# lime2_adapter.net
KiCad netlist of a schematic drawn in EAGLE
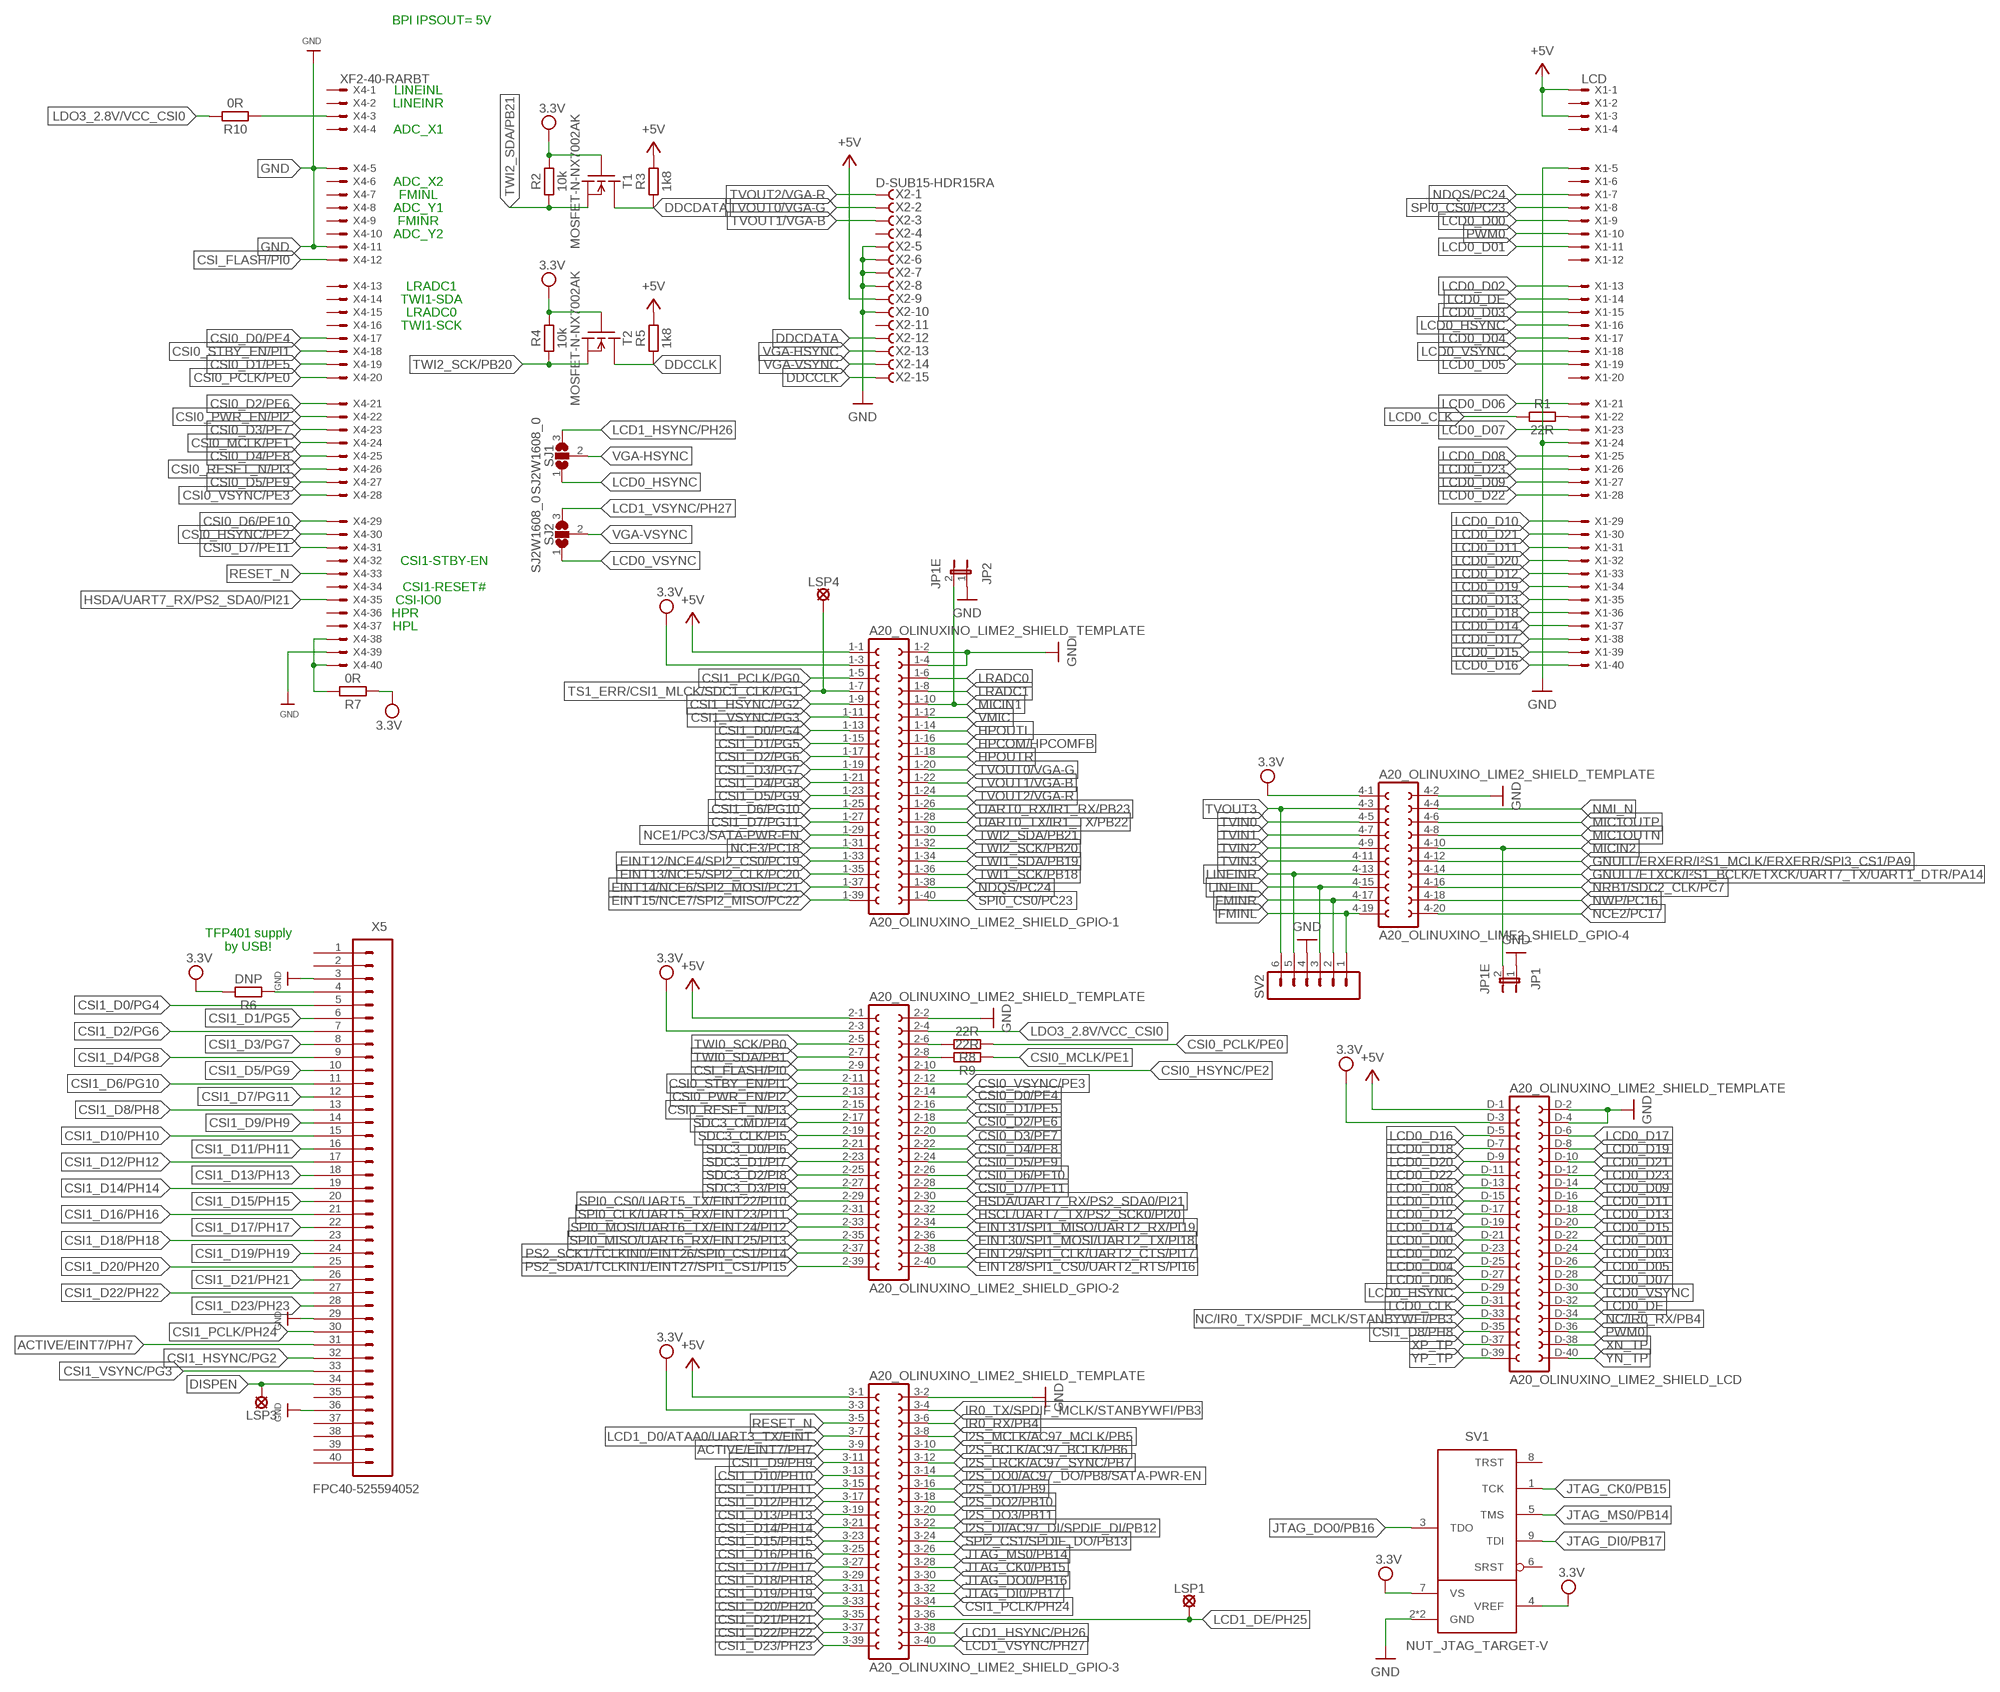
[diagram p0: schematic, sheet 1]

(export (version "E")
  (design (tool "Eeschema 10.0.6"))
  (components
    (comp (ref "A20_OLINUXINO_LIME2_SHIELD")
      (value "A20_OLINUXINO_LIME2_SHIELD_TEMPLATE")
      (footprint "eagle-import:A20_OLINUXINO_LIME2_SHIELD")
      (libsource (lib "eagle-import") (part "A20_OLINUXINO_LIME2_SHIELD_TEMPLATE"))
    )
    (comp (ref "JP1")
      (value "JP1E")
      (footprint "eagle-import:JP1")
      (libsource (lib "eagle-import") (part "JP1E"))
    )
    (comp (ref "JP2")
      (value "JP1E")
      (footprint "eagle-import:JP1")
      (libsource (lib "eagle-import") (part "JP1E"))
    )
    (comp (ref "LSP1")
      (value "LSP-PAD15")
      (footprint "eagle-import:PAD15")
      (libsource (lib "eagle-import") (part "LSP-PAD15"))
    )
    (comp (ref "LSP3")
      (value "LSP-PAD15")
      (footprint "eagle-import:PAD15")
      (libsource (lib "eagle-import") (part "LSP-PAD15"))
    )
    (comp (ref "LSP4")
      (value "LSP-PAD15")
      (footprint "eagle-import:PAD15")
      (libsource (lib "eagle-import") (part "LSP-PAD15"))
    )
    (comp (ref "R1")
      (value "22R")
      (footprint "eagle-import:RES1608X55N")
      (libsource (lib "eagle-import") (part "R-EU_RES1608X55N"))
    )
    (comp (ref "R2")
      (value "10k")
      (footprint "eagle-import:RES1608X55N")
      (libsource (lib "eagle-import") (part "R-EU_RES1608X55N"))
    )
    (comp (ref "R3")
      (value "1k8")
      (footprint "eagle-import:RES1608X55N")
      (libsource (lib "eagle-import") (part "R-EU_RES1608X55N"))
    )
    (comp (ref "R4")
      (value "10k")
      (footprint "eagle-import:RES1608X55N")
      (libsource (lib "eagle-import") (part "R-EU_RES1608X55N"))
    )
    (comp (ref "R5")
      (value "1k8")
      (footprint "eagle-import:RES1608X55N")
      (libsource (lib "eagle-import") (part "R-EU_RES1608X55N"))
    )
    (comp (ref "R6")
      (value "DNP")
      (footprint "eagle-import:RES1608X55N")
      (libsource (lib "eagle-import") (part "R-EU_RES1608X55N"))
    )
    (comp (ref "R7")
      (value "0R")
      (footprint "eagle-import:RES1608X55N")
      (libsource (lib "eagle-import") (part "R-EU_RES1608X55N"))
    )
    (comp (ref "R8")
      (value "22R")
      (footprint "eagle-import:RES1608X55N")
      (libsource (lib "eagle-import") (part "R-EU_RES1608X55N"))
    )
    (comp (ref "R9")
      (value "22R")
      (footprint "eagle-import:RES1608X55N")
      (libsource (lib "eagle-import") (part "R-EU_RES1608X55N"))
    )
    (comp (ref "R10")
      (value "0R")
      (footprint "eagle-import:RES1608X55N")
      (libsource (lib "eagle-import") (part "R-EU_RES1608X55N"))
    )
    (comp (ref "SJ1")
      (value "SJ2W1608_0")
      (footprint "eagle-import:SJ2_1608_0")
      (libsource (lib "eagle-import") (part "SJ2W1608_0"))
    )
    (comp (ref "SJ2")
      (value "SJ2W1608_0")
      (footprint "eagle-import:SJ2_1608_0")
      (libsource (lib "eagle-import") (part "SJ2W1608_0"))
    )
    (comp (ref "SV1")
      (value "NUT_JTAG_TARGET-V")
      (footprint "eagle-import:ML10")
      (libsource (lib "eagle-import") (part "NUT_JTAG_TARGET-V"))
    )
    (comp (ref "SV2")
      (value "MA06-1")
      (footprint "eagle-import:MA06-1")
      (libsource (lib "eagle-import") (part "MA06-1"))
    )
    (comp (ref "T1")
      (value "MOSFET-N-NX7002AK")
      (footprint "eagle-import:SOT95P230X110-3N")
      (libsource (lib "eagle-import") (part "MOSFET-N-?KNX7002A"))
    )
    (comp (ref "T2")
      (value "MOSFET-N-NX7002AK")
      (footprint "eagle-import:SOT95P230X110-3N")
      (libsource (lib "eagle-import") (part "MOSFET-N-?KNX7002A"))
    )
    (comp (ref "X1")
      (value "LCD")
      (footprint "eagle-import:4-1734839-0")
      (libsource (lib "eagle-import") (part "XF2-40?-RARBT"))
    )
    (comp (ref "X2")
      (value "D-SUB15-HDR15RA")
      (footprint "eagle-import:HDR15RA")
      (libsource (lib "eagle-import") (part "D-SUB15-HDR15RA"))
    )
    (comp (ref "X4")
      (value "XF2-40-RARBT")
      (footprint "eagle-import:4-1734839-0")
      (libsource (lib "eagle-import") (part "XF2-40?-RARBT"))
    )
    (comp (ref "X5")
      (value "FPC40-525594052")
      (footprint "eagle-import:525594052")
      (libsource (lib "eagle-import") (part "FPC40-525594052"))
    )
  )
  (nets
    (net (code "1") (name "+5V") (class "Default")
      (node (ref "A20_OLINUXINO_LIME2_SHIELD") (pin "1-1") (pinfunction "1_1-1") (pintype "passive"))
      (node (ref "A20_OLINUXINO_LIME2_SHIELD") (pin "2-1") (pinfunction "1_2-1") (pintype "passive"))
      (node (ref "A20_OLINUXINO_LIME2_SHIELD") (pin "3-1") (pinfunction "1_3-1") (pintype "passive"))
      (node (ref "A20_OLINUXINO_LIME2_SHIELD") (pin "D-1") (pinfunction "1_D-1") (pintype "passive"))
      (node (ref "R3") (pin "2") (pinfunction "2_2") (pintype "passive"))
      (node (ref "R5") (pin "2") (pinfunction "2_2") (pintype "passive"))
      (node (ref "X1") (pin "1") (pinfunction "MSV_1") (pintype "passive"))
      (node (ref "X1") (pin "3") (pinfunction "MS_3") (pintype "passive"))
      (node (ref "X2") (pin "9") (pinfunction "F_9") (pintype "passive"))
    )
    (net (code "2") (name "3.3V") (class "Default")
      (node (ref "A20_OLINUXINO_LIME2_SHIELD") (pin "1-3") (pinfunction "3_1-3") (pintype "passive"))
      (node (ref "A20_OLINUXINO_LIME2_SHIELD") (pin "2-3") (pinfunction "3_2-3") (pintype "passive"))
      (node (ref "A20_OLINUXINO_LIME2_SHIELD") (pin "3-3") (pinfunction "3_3-3") (pintype "passive"))
      (node (ref "A20_OLINUXINO_LIME2_SHIELD") (pin "4-1") (pinfunction "1_4-1") (pintype "passive"))
      (node (ref "A20_OLINUXINO_LIME2_SHIELD") (pin "D-3") (pinfunction "3_D-3") (pintype "passive"))
      (node (ref "R2") (pin "2") (pinfunction "2_2") (pintype "passive"))
      (node (ref "R4") (pin "2") (pinfunction "2_2") (pintype "passive"))
      (node (ref "R6") (pin "2") (pinfunction "2_2") (pintype "passive"))
      (node (ref "R7") (pin "1") (pinfunction "1_1") (pintype "passive"))
      (node (ref "SV1") (pin "4") (pinfunction "VREF_4") (pintype "input"))
      (node (ref "SV1") (pin "7") (pinfunction "VS_7") (pintype "passive"))
      (node (ref "T1") (pin "1") (pinfunction "G_1") (pintype "passive"))
      (node (ref "T2") (pin "1") (pinfunction "G_1") (pintype "passive"))
    )
    (net (code "3") (name "ACTIVE{slash}EINT7{slash}PH7") (class "Default")
      (node (ref "A20_OLINUXINO_LIME2_SHIELD") (pin "3-9") (pinfunction "9_3-9") (pintype "passive"))
      (node (ref "X5") (pin "31") (pinfunction "31_31") (pintype "passive"))
    )
    (net (code "4") (name "CSI0_D0{slash}PE4") (class "Default")
      (node (ref "A20_OLINUXINO_LIME2_SHIELD") (pin "2-14") (pinfunction "14_2-14") (pintype "passive"))
      (node (ref "X4") (pin "17") (pinfunction "MS_17") (pintype "passive"))
    )
    (net (code "5") (name "CSI0_D1{slash}PE5") (class "Default")
      (node (ref "A20_OLINUXINO_LIME2_SHIELD") (pin "2-16") (pinfunction "16_2-16") (pintype "passive"))
      (node (ref "X4") (pin "19") (pinfunction "MS_19") (pintype "passive"))
    )
    (net (code "6") (name "CSI0_D2{slash}PE6") (class "Default")
      (node (ref "A20_OLINUXINO_LIME2_SHIELD") (pin "2-18") (pinfunction "18_2-18") (pintype "passive"))
      (node (ref "X4") (pin "21") (pinfunction "MS_21") (pintype "passive"))
    )
    (net (code "7") (name "CSI0_D3{slash}PE7") (class "Default")
      (node (ref "A20_OLINUXINO_LIME2_SHIELD") (pin "2-20") (pinfunction "20_2-20") (pintype "passive"))
      (node (ref "X4") (pin "23") (pinfunction "MS_23") (pintype "passive"))
    )
    (net (code "8") (name "CSI0_D4{slash}PE8") (class "Default")
      (node (ref "A20_OLINUXINO_LIME2_SHIELD") (pin "2-22") (pinfunction "22_2-22") (pintype "passive"))
      (node (ref "X4") (pin "25") (pinfunction "MS_25") (pintype "passive"))
    )
    (net (code "9") (name "CSI0_D5{slash}PE9") (class "Default")
      (node (ref "A20_OLINUXINO_LIME2_SHIELD") (pin "2-24") (pinfunction "24_2-24") (pintype "passive"))
      (node (ref "X4") (pin "27") (pinfunction "MS_27") (pintype "passive"))
    )
    (net (code "10") (name "CSI0_D6{slash}PE10") (class "Default")
      (node (ref "A20_OLINUXINO_LIME2_SHIELD") (pin "2-26") (pinfunction "26_2-26") (pintype "passive"))
      (node (ref "X4") (pin "29") (pinfunction "MS_29") (pintype "passive"))
    )
    (net (code "11") (name "CSI0_D7{slash}PE11") (class "Default")
      (node (ref "A20_OLINUXINO_LIME2_SHIELD") (pin "2-28") (pinfunction "28_2-28") (pintype "passive"))
      (node (ref "X4") (pin "31") (pinfunction "MS_31") (pintype "passive"))
    )
    (net (code "12") (name "CSI0_HSYNC{slash}PE2") (class "Default")
      (node (ref "A20_OLINUXINO_LIME2_SHIELD") (pin "2-10") (pinfunction "10_2-10") (pintype "passive"))
      (node (ref "X4") (pin "30") (pinfunction "MS_30") (pintype "passive"))
    )
    (net (code "13") (name "CSI0_MCLK{slash}PE1") (class "Default")
      (node (ref "R9") (pin "1") (pinfunction "1_1") (pintype "passive"))
      (node (ref "X4") (pin "24") (pinfunction "MS_24") (pintype "passive"))
    )
    (net (code "14") (name "CSI0_PCLK{slash}PE0") (class "Default")
      (node (ref "R8") (pin "1") (pinfunction "1_1") (pintype "passive"))
      (node (ref "X4") (pin "20") (pinfunction "MS_20") (pintype "passive"))
    )
    (net (code "15") (name "CSI0_PWR_EN{slash}PI2") (class "Default")
      (node (ref "A20_OLINUXINO_LIME2_SHIELD") (pin "2-13") (pinfunction "13_2-13") (pintype "passive"))
      (node (ref "X4") (pin "22") (pinfunction "MS_22") (pintype "passive"))
    )
    (net (code "16") (name "CSI0_RESET_N{slash}PI3") (class "Default")
      (node (ref "A20_OLINUXINO_LIME2_SHIELD") (pin "2-15") (pinfunction "15_2-15") (pintype "passive"))
      (node (ref "X4") (pin "26") (pinfunction "MS_26") (pintype "passive"))
    )
    (net (code "17") (name "CSI0_STBY_EN{slash}PI1") (class "Default")
      (node (ref "A20_OLINUXINO_LIME2_SHIELD") (pin "2-11") (pinfunction "11_2-11") (pintype "passive"))
      (node (ref "X4") (pin "18") (pinfunction "MS_18") (pintype "passive"))
    )
    (net (code "18") (name "CSI0_VSYNC{slash}PE3") (class "Default")
      (node (ref "A20_OLINUXINO_LIME2_SHIELD") (pin "2-12") (pinfunction "12_2-12") (pintype "passive"))
      (node (ref "X4") (pin "28") (pinfunction "MS_28") (pintype "passive"))
    )
    (net (code "19") (name "CSI1_D0{slash}PG4") (class "Default")
      (node (ref "A20_OLINUXINO_LIME2_SHIELD") (pin "1-13") (pinfunction "13_1-13") (pintype "passive"))
      (node (ref "X5") (pin "5") (pinfunction "5_5") (pintype "passive"))
    )
    (net (code "20") (name "CSI1_D1{slash}PG5") (class "Default")
      (node (ref "A20_OLINUXINO_LIME2_SHIELD") (pin "1-15") (pinfunction "15_1-15") (pintype "passive"))
      (node (ref "X5") (pin "6") (pinfunction "6_6") (pintype "passive"))
    )
    (net (code "21") (name "CSI1_D2{slash}PG6") (class "Default")
      (node (ref "A20_OLINUXINO_LIME2_SHIELD") (pin "1-17") (pinfunction "17_1-17") (pintype "passive"))
      (node (ref "X5") (pin "7") (pinfunction "7_7") (pintype "passive"))
    )
    (net (code "22") (name "CSI1_D3{slash}PG7") (class "Default")
      (node (ref "A20_OLINUXINO_LIME2_SHIELD") (pin "1-19") (pinfunction "19_1-19") (pintype "passive"))
      (node (ref "X5") (pin "8") (pinfunction "8_8") (pintype "passive"))
    )
    (net (code "23") (name "CSI1_D4{slash}PG8") (class "Default")
      (node (ref "A20_OLINUXINO_LIME2_SHIELD") (pin "1-21") (pinfunction "21_1-21") (pintype "passive"))
      (node (ref "X5") (pin "9") (pinfunction "9_9") (pintype "passive"))
    )
    (net (code "24") (name "CSI1_D5{slash}PG9") (class "Default")
      (node (ref "A20_OLINUXINO_LIME2_SHIELD") (pin "1-23") (pinfunction "23_1-23") (pintype "passive"))
      (node (ref "X5") (pin "10") (pinfunction "10_10") (pintype "passive"))
    )
    (net (code "25") (name "CSI1_D6{slash}PG10") (class "Default")
      (node (ref "A20_OLINUXINO_LIME2_SHIELD") (pin "1-25") (pinfunction "25_1-25") (pintype "passive"))
      (node (ref "X5") (pin "11") (pinfunction "11_11") (pintype "passive"))
    )
    (net (code "26") (name "CSI1_D7{slash}PG11") (class "Default")
      (node (ref "A20_OLINUXINO_LIME2_SHIELD") (pin "1-27") (pinfunction "27_1-27") (pintype "passive"))
      (node (ref "X5") (pin "12") (pinfunction "12_12") (pintype "passive"))
    )
    (net (code "27") (name "CSI1_D8{slash}PH8") (class "Default")
      (node (ref "A20_OLINUXINO_LIME2_SHIELD") (pin "D-35") (pinfunction "35_D-35") (pintype "passive"))
      (node (ref "X5") (pin "13") (pinfunction "13_13") (pintype "passive"))
    )
    (net (code "28") (name "CSI1_D9{slash}PH9") (class "Default")
      (node (ref "A20_OLINUXINO_LIME2_SHIELD") (pin "3-11") (pinfunction "11_3-11") (pintype "passive"))
      (node (ref "X5") (pin "14") (pinfunction "14_14") (pintype "passive"))
    )
    (net (code "29") (name "CSI1_D10{slash}PH10") (class "Default")
      (node (ref "A20_OLINUXINO_LIME2_SHIELD") (pin "3-13") (pinfunction "13_3-13") (pintype "passive"))
      (node (ref "X5") (pin "15") (pinfunction "15_15") (pintype "passive"))
    )
    (net (code "30") (name "CSI1_D11{slash}PH11") (class "Default")
      (node (ref "A20_OLINUXINO_LIME2_SHIELD") (pin "3-15") (pinfunction "15_3-15") (pintype "passive"))
      (node (ref "X5") (pin "16") (pinfunction "16_16") (pintype "passive"))
    )
    (net (code "31") (name "CSI1_D12{slash}PH12") (class "Default")
      (node (ref "A20_OLINUXINO_LIME2_SHIELD") (pin "3-17") (pinfunction "17_3-17") (pintype "passive"))
      (node (ref "X5") (pin "17") (pinfunction "17_17") (pintype "passive"))
    )
    (net (code "32") (name "CSI1_D13{slash}PH13") (class "Default")
      (node (ref "A20_OLINUXINO_LIME2_SHIELD") (pin "3-19") (pinfunction "19_3-19") (pintype "passive"))
      (node (ref "X5") (pin "18") (pinfunction "18_18") (pintype "passive"))
    )
    (net (code "33") (name "CSI1_D14{slash}PH14") (class "Default")
      (node (ref "A20_OLINUXINO_LIME2_SHIELD") (pin "3-21") (pinfunction "21_3-21") (pintype "passive"))
      (node (ref "X5") (pin "19") (pinfunction "19_19") (pintype "passive"))
    )
    (net (code "34") (name "CSI1_D15{slash}PH15") (class "Default")
      (node (ref "A20_OLINUXINO_LIME2_SHIELD") (pin "3-23") (pinfunction "23_3-23") (pintype "passive"))
      (node (ref "X5") (pin "20") (pinfunction "20_20") (pintype "passive"))
    )
    (net (code "35") (name "CSI1_D16{slash}PH16") (class "Default")
      (node (ref "A20_OLINUXINO_LIME2_SHIELD") (pin "3-25") (pinfunction "25_3-25") (pintype "passive"))
      (node (ref "X5") (pin "21") (pinfunction "21_21") (pintype "passive"))
    )
    (net (code "36") (name "CSI1_D17{slash}PH17") (class "Default")
      (node (ref "A20_OLINUXINO_LIME2_SHIELD") (pin "3-27") (pinfunction "27_3-27") (pintype "passive"))
      (node (ref "X5") (pin "22") (pinfunction "22_22") (pintype "passive"))
    )
    (net (code "37") (name "CSI1_D18{slash}PH18") (class "Default")
      (node (ref "A20_OLINUXINO_LIME2_SHIELD") (pin "3-29") (pinfunction "29_3-29") (pintype "passive"))
      (node (ref "X5") (pin "23") (pinfunction "23_23") (pintype "passive"))
    )
    (net (code "38") (name "CSI1_D19{slash}PH19") (class "Default")
      (node (ref "A20_OLINUXINO_LIME2_SHIELD") (pin "3-31") (pinfunction "31_3-31") (pintype "passive"))
      (node (ref "X5") (pin "24") (pinfunction "24_24") (pintype "passive"))
    )
    (net (code "39") (name "CSI1_D20{slash}PH20") (class "Default")
      (node (ref "A20_OLINUXINO_LIME2_SHIELD") (pin "3-33") (pinfunction "33_3-33") (pintype "passive"))
      (node (ref "X5") (pin "25") (pinfunction "25_25") (pintype "passive"))
    )
    (net (code "40") (name "CSI1_D21{slash}PH21") (class "Default")
      (node (ref "A20_OLINUXINO_LIME2_SHIELD") (pin "3-35") (pinfunction "35_3-35") (pintype "passive"))
      (node (ref "X5") (pin "26") (pinfunction "26_26") (pintype "passive"))
    )
    (net (code "41") (name "CSI1_D22{slash}PH22") (class "Default")
      (node (ref "A20_OLINUXINO_LIME2_SHIELD") (pin "3-37") (pinfunction "37_3-37") (pintype "passive"))
      (node (ref "X5") (pin "27") (pinfunction "27_27") (pintype "passive"))
    )
    (net (code "42") (name "CSI1_D23{slash}PH23") (class "Default")
      (node (ref "A20_OLINUXINO_LIME2_SHIELD") (pin "3-39") (pinfunction "39_3-39") (pintype "passive"))
      (node (ref "X5") (pin "28") (pinfunction "28_28") (pintype "passive"))
    )
    (net (code "43") (name "CSI1_HSYNC{slash}PG2") (class "Default")
      (node (ref "A20_OLINUXINO_LIME2_SHIELD") (pin "1-9") (pinfunction "9_1-9") (pintype "passive"))
      (node (ref "X5") (pin "32") (pinfunction "32_32") (pintype "passive"))
    )
    (net (code "44") (name "CSI1_PCLK{slash}PG0") (class "Default")
      (node (ref "A20_OLINUXINO_LIME2_SHIELD") (pin "1-5") (pinfunction "5_1-5") (pintype "passive"))
    )
    (net (code "45") (name "CSI1_PCLK{slash}PH24") (class "Default")
      (node (ref "A20_OLINUXINO_LIME2_SHIELD") (pin "3-34") (pinfunction "34_3-34") (pintype "passive"))
      (node (ref "X5") (pin "30") (pinfunction "30_30") (pintype "passive"))
    )
    (net (code "46") (name "CSI1_VSYNC{slash}PG3") (class "Default")
      (node (ref "A20_OLINUXINO_LIME2_SHIELD") (pin "1-11") (pinfunction "11_1-11") (pintype "passive"))
      (node (ref "X5") (pin "33") (pinfunction "33_33") (pintype "passive"))
    )
    (net (code "47") (name "CSI_FLASH{slash}PI0") (class "Default")
      (node (ref "A20_OLINUXINO_LIME2_SHIELD") (pin "2-9") (pinfunction "9_2-9") (pintype "passive"))
      (node (ref "X4") (pin "12") (pinfunction "MS_12") (pintype "passive"))
    )
    (net (code "48") (name "DDCCLK") (class "Default")
      (node (ref "R5") (pin "1") (pinfunction "1_1") (pintype "passive"))
      (node (ref "T2") (pin "3") (pinfunction "D_3") (pintype "passive"))
      (node (ref "X2") (pin "15") (pinfunction "F_15") (pintype "passive"))
    )
    (net (code "49") (name "DDCDATA") (class "Default")
      (node (ref "R3") (pin "1") (pinfunction "1_1") (pintype "passive"))
      (node (ref "T1") (pin "3") (pinfunction "D_3") (pintype "passive"))
      (node (ref "X2") (pin "12") (pinfunction "F_12") (pintype "passive"))
    )
    (net (code "50") (name "DISPEN") (class "Default")
      (node (ref "LSP3") (pin "MP") (pinfunction "MP_MP") (pintype "passive"))
      (node (ref "X5") (pin "34") (pinfunction "34_34") (pintype "passive"))
    )
    (net (code "51") (name "EINT12{slash}NCE4{slash}SPI2_CS0{slash}PC19") (class "Default")
      (node (ref "A20_OLINUXINO_LIME2_SHIELD") (pin "1-33") (pinfunction "33_1-33") (pintype "passive"))
    )
    (net (code "52") (name "EINT13{slash}NCE5{slash}SPI2_CLK{slash}PC20") (class "Default")
      (node (ref "A20_OLINUXINO_LIME2_SHIELD") (pin "1-35") (pinfunction "35_1-35") (pintype "passive"))
    )
    (net (code "53") (name "EINT14{slash}NCE6{slash}SPI2_MOSI{slash}PC21") (class "Default")
      (node (ref "A20_OLINUXINO_LIME2_SHIELD") (pin "1-37") (pinfunction "37_1-37") (pintype "passive"))
    )
    (net (code "54") (name "EINT15{slash}NCE7{slash}SPI2_MISO{slash}PC22") (class "Default")
      (node (ref "A20_OLINUXINO_LIME2_SHIELD") (pin "1-39") (pinfunction "39_1-39") (pintype "passive"))
    )
    (net (code "55") (name "EINT28{slash}SPI1_CS0{slash}UART2_RTS{slash}PI16") (class "Default")
      (node (ref "A20_OLINUXINO_LIME2_SHIELD") (pin "2-40") (pinfunction "40_2-40") (pintype "passive"))
    )
    (net (code "56") (name "EINT29{slash}SPI1_CLK{slash}UART2_CTS{slash}PI17") (class "Default")
      (node (ref "A20_OLINUXINO_LIME2_SHIELD") (pin "2-38") (pinfunction "38_2-38") (pintype "passive"))
    )
    (net (code "57") (name "EINT30{slash}SPI1_MOSI{slash}UART2_TX{slash}PI18") (class "Default")
      (node (ref "A20_OLINUXINO_LIME2_SHIELD") (pin "2-36") (pinfunction "36_2-36") (pintype "passive"))
    )
    (net (code "58") (name "EINT31{slash}SPI1_MISO{slash}UART2_RX{slash}PI19") (class "Default")
      (node (ref "A20_OLINUXINO_LIME2_SHIELD") (pin "2-34") (pinfunction "34_2-34") (pintype "passive"))
    )
    (net (code "59") (name "FMINL") (class "Default")
      (node (ref "A20_OLINUXINO_LIME2_SHIELD") (pin "4-19") (pinfunction "19_4-19") (pintype "passive"))
      (node (ref "SV2") (pin "1") (pinfunction "1_1") (pintype "passive"))
    )
    (net (code "60") (name "FMINR") (class "Default")
      (node (ref "A20_OLINUXINO_LIME2_SHIELD") (pin "4-17") (pinfunction "17_4-17") (pintype "passive"))
      (node (ref "SV2") (pin "2") (pinfunction "2_2") (pintype "passive"))
    )
    (net (code "61") (name "GND") (class "Default")
      (node (ref "A20_OLINUXINO_LIME2_SHIELD") (pin "1-2") (pinfunction "2_1-2") (pintype "passive"))
      (node (ref "A20_OLINUXINO_LIME2_SHIELD") (pin "1-4") (pinfunction "4_1-4") (pintype "passive"))
      (node (ref "A20_OLINUXINO_LIME2_SHIELD") (pin "2-2") (pinfunction "2_2-2") (pintype "passive"))
      (node (ref "A20_OLINUXINO_LIME2_SHIELD") (pin "3-2") (pinfunction "2_3-2") (pintype "passive"))
      (node (ref "A20_OLINUXINO_LIME2_SHIELD") (pin "4-2") (pinfunction "2_4-2") (pintype "passive"))
      (node (ref "A20_OLINUXINO_LIME2_SHIELD") (pin "D-2") (pinfunction "2_D-2") (pintype "passive"))
      (node (ref "A20_OLINUXINO_LIME2_SHIELD") (pin "D-4") (pinfunction "4_D-4") (pintype "passive"))
      (node (ref "JP1") (pin "1") (pinfunction "1_1") (pintype "passive"))
      (node (ref "JP2") (pin "1") (pinfunction "1_1") (pintype "passive"))
      (node (ref "SV1") (pin "10") (pinfunction "GND_10") (pintype "power_in"))
      (node (ref "SV1") (pin "2") (pinfunction "GND_2") (pintype "power_in"))
      (node (ref "SV2") (pin "4") (pinfunction "4_4") (pintype "passive"))
      (node (ref "X1") (pin "24") (pinfunction "MS_24") (pintype "passive"))
      (node (ref "X1") (pin "5") (pinfunction "MS_5") (pintype "passive"))
      (node (ref "X2") (pin "10") (pinfunction "F_10") (pintype "passive"))
      (node (ref "X2") (pin "5") (pinfunction "F_5") (pintype "passive"))
      (node (ref "X2") (pin "6") (pinfunction "F_6") (pintype "passive"))
      (node (ref "X2") (pin "7") (pinfunction "F_7") (pintype "passive"))
      (node (ref "X2") (pin "8") (pinfunction "F_8") (pintype "passive"))
      (node (ref "X4") (pin "11") (pinfunction "MS_11") (pintype "passive"))
      (node (ref "X4") (pin "39") (pinfunction "MS_39") (pintype "passive"))
      (node (ref "X4") (pin "5") (pinfunction "MS_5") (pintype "passive"))
      (node (ref "X5") (pin "29") (pinfunction "29_29") (pintype "passive"))
      (node (ref "X5") (pin "3") (pinfunction "3_3") (pintype "passive"))
      (node (ref "X5") (pin "36") (pinfunction "36_36") (pintype "passive"))
    )
    (net (code "62") (name "GNULL{slash}ERXERR{slash}I²S1_MCLK{slash}ERXERR{slash}SPI3_CS1{slash}PA9") (class "Default")
      (node (ref "A20_OLINUXINO_LIME2_SHIELD") (pin "4-12") (pinfunction "12_4-12") (pintype "passive"))
    )
    (net (code "63") (name "GNULL{slash}ETXCK{slash}I²S1_BCLK{slash}ETXCK{slash}UART7_TX{slash}UART1_DTR{slash}PA14") (class "Default")
      (node (ref "A20_OLINUXINO_LIME2_SHIELD") (pin "4-14") (pinfunction "14_4-14") (pintype "passive"))
    )
    (net (code "64") (name "HPCOM{slash}HPCOMFB") (class "Default")
      (node (ref "A20_OLINUXINO_LIME2_SHIELD") (pin "1-16") (pinfunction "16_1-16") (pintype "passive"))
    )
    (net (code "65") (name "HPOUTL") (class "Default")
      (node (ref "A20_OLINUXINO_LIME2_SHIELD") (pin "1-14") (pinfunction "14_1-14") (pintype "passive"))
    )
    (net (code "66") (name "HPOUTR") (class "Default")
      (node (ref "A20_OLINUXINO_LIME2_SHIELD") (pin "1-18") (pinfunction "18_1-18") (pintype "passive"))
    )
    (net (code "67") (name "HSCL{slash}UART7_TX{slash}PS2_SCK0{slash}PI20") (class "Default")
      (node (ref "A20_OLINUXINO_LIME2_SHIELD") (pin "2-32") (pinfunction "32_2-32") (pintype "passive"))
    )
    (net (code "68") (name "HSDA{slash}UART7_RX{slash}PS2_SDA0{slash}PI21") (class "Default")
      (node (ref "A20_OLINUXINO_LIME2_SHIELD") (pin "2-30") (pinfunction "30_2-30") (pintype "passive"))
      (node (ref "X4") (pin "35") (pinfunction "MS_35") (pintype "passive"))
    )
    (net (code "69") (name "I2S_BCLK{slash}AC97_BCLK{slash}PB6") (class "Default")
      (node (ref "A20_OLINUXINO_LIME2_SHIELD") (pin "3-10") (pinfunction "10_3-10") (pintype "passive"))
    )
    (net (code "70") (name "I2S_DI{slash}AC97_DI{slash}SPDIF_DI{slash}PB12") (class "Default")
      (node (ref "A20_OLINUXINO_LIME2_SHIELD") (pin "3-22") (pinfunction "22_3-22") (pintype "passive"))
    )
    (net (code "71") (name "I2S_DO0{slash}AC97_DO{slash}PB8{slash}SATA-PWR-EN") (class "Default")
      (node (ref "A20_OLINUXINO_LIME2_SHIELD") (pin "3-14") (pinfunction "14_3-14") (pintype "passive"))
    )
    (net (code "72") (name "I2S_DO1{slash}PB9") (class "Default")
      (node (ref "A20_OLINUXINO_LIME2_SHIELD") (pin "3-16") (pinfunction "16_3-16") (pintype "passive"))
    )
    (net (code "73") (name "I2S_DO2{slash}PB10") (class "Default")
      (node (ref "A20_OLINUXINO_LIME2_SHIELD") (pin "3-18") (pinfunction "18_3-18") (pintype "passive"))
    )
    (net (code "74") (name "I2S_DO3{slash}PB11") (class "Default")
      (node (ref "A20_OLINUXINO_LIME2_SHIELD") (pin "3-20") (pinfunction "20_3-20") (pintype "passive"))
    )
    (net (code "75") (name "I2S_LRCK{slash}AC97_SYNC{slash}PB7") (class "Default")
      (node (ref "A20_OLINUXINO_LIME2_SHIELD") (pin "3-12") (pinfunction "12_3-12") (pintype "passive"))
    )
    (net (code "76") (name "I2S_MCLK{slash}AC97_MCLK{slash}PB5") (class "Default")
      (node (ref "A20_OLINUXINO_LIME2_SHIELD") (pin "3-8") (pinfunction "8_3-8") (pintype "passive"))
    )
    (net (code "77") (name "IR0_RX{slash}PB4") (class "Default")
      (node (ref "A20_OLINUXINO_LIME2_SHIELD") (pin "3-6") (pinfunction "6_3-6") (pintype "passive"))
    )
    (net (code "78") (name "IR0_TX{slash}SPDIF_MCLK{slash}STANBYWFI{slash}PB3") (class "Default")
      (node (ref "A20_OLINUXINO_LIME2_SHIELD") (pin "3-4") (pinfunction "4_3-4") (pintype "passive"))
    )
    (net (code "79") (name "JTAG_CK0{slash}PB15") (class "Default")
      (node (ref "A20_OLINUXINO_LIME2_SHIELD") (pin "3-28") (pinfunction "28_3-28") (pintype "passive"))
      (node (ref "SV1") (pin "1") (pinfunction "TCK_1") (pintype "output"))
    )
    (net (code "80") (name "JTAG_DI0{slash}PB17") (class "Default")
      (node (ref "A20_OLINUXINO_LIME2_SHIELD") (pin "3-32") (pinfunction "32_3-32") (pintype "passive"))
      (node (ref "SV1") (pin "9") (pinfunction "TDI_9") (pintype "output"))
    )
    (net (code "81") (name "JTAG_DO0{slash}PB16") (class "Default")
      (node (ref "A20_OLINUXINO_LIME2_SHIELD") (pin "3-30") (pinfunction "30_3-30") (pintype "passive"))
      (node (ref "SV1") (pin "3") (pinfunction "TDO_3") (pintype "input"))
    )
    (net (code "82") (name "JTAG_MS0{slash}PB14") (class "Default")
      (node (ref "A20_OLINUXINO_LIME2_SHIELD") (pin "3-26") (pinfunction "26_3-26") (pintype "passive"))
      (node (ref "SV1") (pin "5") (pinfunction "TMS_5") (pintype "output"))
    )
    (net (code "83") (name "LCD0_CLK") (class "Default")
      (node (ref "A20_OLINUXINO_LIME2_SHIELD") (pin "D-31") (pinfunction "31_D-31") (pintype "passive"))
      (node (ref "R1") (pin "1") (pinfunction "1_1") (pintype "passive"))
    )
    (net (code "84") (name "LCD0_D00") (class "Default")
      (node (ref "A20_OLINUXINO_LIME2_SHIELD") (pin "D-21") (pinfunction "21_D-21") (pintype "passive"))
      (node (ref "X1") (pin "9") (pinfunction "MS_9") (pintype "passive"))
    )
    (net (code "85") (name "LCD0_D01") (class "Default")
      (node (ref "A20_OLINUXINO_LIME2_SHIELD") (pin "D-22") (pinfunction "22_D-22") (pintype "passive"))
      (node (ref "X1") (pin "11") (pinfunction "MS_11") (pintype "passive"))
    )
    (net (code "86") (name "LCD0_D02") (class "Default")
      (node (ref "A20_OLINUXINO_LIME2_SHIELD") (pin "D-23") (pinfunction "23_D-23") (pintype "passive"))
      (node (ref "X1") (pin "13") (pinfunction "MS_13") (pintype "passive"))
    )
    (net (code "87") (name "LCD0_D03") (class "Default")
      (node (ref "A20_OLINUXINO_LIME2_SHIELD") (pin "D-24") (pinfunction "24_D-24") (pintype "passive"))
      (node (ref "X1") (pin "15") (pinfunction "MS_15") (pintype "passive"))
    )
    (net (code "88") (name "LCD0_D04") (class "Default")
      (node (ref "A20_OLINUXINO_LIME2_SHIELD") (pin "D-25") (pinfunction "25_D-25") (pintype "passive"))
      (node (ref "X1") (pin "17") (pinfunction "MS_17") (pintype "passive"))
    )
    (net (code "89") (name "LCD0_D05") (class "Default")
      (node (ref "A20_OLINUXINO_LIME2_SHIELD") (pin "D-26") (pinfunction "26_D-26") (pintype "passive"))
      (node (ref "X1") (pin "19") (pinfunction "MS_19") (pintype "passive"))
    )
    (net (code "90") (name "LCD0_D06") (class "Default")
      (node (ref "A20_OLINUXINO_LIME2_SHIELD") (pin "D-27") (pinfunction "27_D-27") (pintype "passive"))
      (node (ref "X1") (pin "21") (pinfunction "MS_21") (pintype "passive"))
    )
    (net (code "91") (name "LCD0_D07") (class "Default")
      (node (ref "A20_OLINUXINO_LIME2_SHIELD") (pin "D-28") (pinfunction "28_D-28") (pintype "passive"))
      (node (ref "X1") (pin "23") (pinfunction "MS_23") (pintype "passive"))
    )
    (net (code "92") (name "LCD0_D08") (class "Default")
      (node (ref "A20_OLINUXINO_LIME2_SHIELD") (pin "D-13") (pinfunction "13_D-13") (pintype "passive"))
      (node (ref "X1") (pin "25") (pinfunction "MS_25") (pintype "passive"))
    )
    (net (code "93") (name "LCD0_D09") (class "Default")
      (node (ref "A20_OLINUXINO_LIME2_SHIELD") (pin "D-14") (pinfunction "14_D-14") (pintype "passive"))
      (node (ref "X1") (pin "27") (pinfunction "MS_27") (pintype "passive"))
    )
    (net (code "94") (name "LCD0_D10") (class "Default")
      (node (ref "A20_OLINUXINO_LIME2_SHIELD") (pin "D-15") (pinfunction "15_D-15") (pintype "passive"))
      (node (ref "X1") (pin "29") (pinfunction "MS_29") (pintype "passive"))
    )
    (net (code "95") (name "LCD0_D11") (class "Default")
      (node (ref "A20_OLINUXINO_LIME2_SHIELD") (pin "D-16") (pinfunction "16_D-16") (pintype "passive"))
      (node (ref "X1") (pin "31") (pinfunction "MS_31") (pintype "passive"))
    )
    (net (code "96") (name "LCD0_D12") (class "Default")
      (node (ref "A20_OLINUXINO_LIME2_SHIELD") (pin "D-17") (pinfunction "17_D-17") (pintype "passive"))
      (node (ref "X1") (pin "33") (pinfunction "MS_33") (pintype "passive"))
    )
    (net (code "97") (name "LCD0_D13") (class "Default")
      (node (ref "A20_OLINUXINO_LIME2_SHIELD") (pin "D-18") (pinfunction "18_D-18") (pintype "passive"))
      (node (ref "X1") (pin "35") (pinfunction "MS_35") (pintype "passive"))
    )
    (net (code "98") (name "LCD0_D14") (class "Default")
      (node (ref "A20_OLINUXINO_LIME2_SHIELD") (pin "D-19") (pinfunction "19_D-19") (pintype "passive"))
      (node (ref "X1") (pin "37") (pinfunction "MS_37") (pintype "passive"))
    )
    (net (code "99") (name "LCD0_D15") (class "Default")
      (node (ref "A20_OLINUXINO_LIME2_SHIELD") (pin "D-20") (pinfunction "20_D-20") (pintype "passive"))
      (node (ref "X1") (pin "39") (pinfunction "MS_39") (pintype "passive"))
    )
    (net (code "100") (name "LCD0_D16") (class "Default")
      (node (ref "A20_OLINUXINO_LIME2_SHIELD") (pin "D-5") (pinfunction "5_D-5") (pintype "passive"))
      (node (ref "X1") (pin "40") (pinfunction "MS_40") (pintype "passive"))
    )
    (net (code "101") (name "LCD0_D17") (class "Default")
      (node (ref "A20_OLINUXINO_LIME2_SHIELD") (pin "D-6") (pinfunction "6_D-6") (pintype "passive"))
      (node (ref "X1") (pin "38") (pinfunction "MS_38") (pintype "passive"))
    )
    (net (code "102") (name "LCD0_D18") (class "Default")
      (node (ref "A20_OLINUXINO_LIME2_SHIELD") (pin "D-7") (pinfunction "7_D-7") (pintype "passive"))
      (node (ref "X1") (pin "36") (pinfunction "MS_36") (pintype "passive"))
    )
    (net (code "103") (name "LCD0_D19") (class "Default")
      (node (ref "A20_OLINUXINO_LIME2_SHIELD") (pin "D-8") (pinfunction "8_D-8") (pintype "passive"))
      (node (ref "X1") (pin "34") (pinfunction "MS_34") (pintype "passive"))
    )
    (net (code "104") (name "LCD0_D20") (class "Default")
      (node (ref "A20_OLINUXINO_LIME2_SHIELD") (pin "D-9") (pinfunction "9_D-9") (pintype "passive"))
      (node (ref "X1") (pin "32") (pinfunction "MS_32") (pintype "passive"))
    )
    (net (code "105") (name "LCD0_D21") (class "Default")
      (node (ref "A20_OLINUXINO_LIME2_SHIELD") (pin "D-10") (pinfunction "10_D-10") (pintype "passive"))
      (node (ref "X1") (pin "30") (pinfunction "MS_30") (pintype "passive"))
    )
    (net (code "106") (name "LCD0_D22") (class "Default")
      (node (ref "A20_OLINUXINO_LIME2_SHIELD") (pin "D-11") (pinfunction "11_D-11") (pintype "passive"))
      (node (ref "X1") (pin "28") (pinfunction "MS_28") (pintype "passive"))
    )
    (net (code "107") (name "LCD0_D23") (class "Default")
      (node (ref "A20_OLINUXINO_LIME2_SHIELD") (pin "D-12") (pinfunction "12_D-12") (pintype "passive"))
      (node (ref "X1") (pin "26") (pinfunction "MS_26") (pintype "passive"))
    )
    (net (code "108") (name "LCD0_DE") (class "Default")
      (node (ref "A20_OLINUXINO_LIME2_SHIELD") (pin "D-32") (pinfunction "32_D-32") (pintype "passive"))
      (node (ref "X1") (pin "14") (pinfunction "MS_14") (pintype "passive"))
    )
    (net (code "109") (name "LCD0_HSYNC") (class "Default")
      (node (ref "A20_OLINUXINO_LIME2_SHIELD") (pin "D-29") (pinfunction "29_D-29") (pintype "passive"))
      (node (ref "SJ1") (pin "1") (pinfunction "1_1") (pintype "passive"))
      (node (ref "X1") (pin "16") (pinfunction "MS_16") (pintype "passive"))
    )
    (net (code "110") (name "LCD0_VSYNC") (class "Default")
      (node (ref "A20_OLINUXINO_LIME2_SHIELD") (pin "D-30") (pinfunction "30_D-30") (pintype "passive"))
      (node (ref "SJ2") (pin "1") (pinfunction "1_1") (pintype "passive"))
      (node (ref "X1") (pin "18") (pinfunction "MS_18") (pintype "passive"))
    )
    (net (code "111") (name "LCD1_D0{slash}ATAA0{slash}UART3_TX{slash}EINT") (class "Default")
      (node (ref "A20_OLINUXINO_LIME2_SHIELD") (pin "3-7") (pinfunction "7_3-7") (pintype "passive"))
    )
    (net (code "112") (name "LCD1_DE{slash}PH25") (class "Default")
      (node (ref "A20_OLINUXINO_LIME2_SHIELD") (pin "3-36") (pinfunction "36_3-36") (pintype "passive"))
      (node (ref "LSP1") (pin "MP") (pinfunction "MP_MP") (pintype "passive"))
    )
    (net (code "113") (name "LCD1_HSYNC{slash}PH26") (class "Default")
      (node (ref "A20_OLINUXINO_LIME2_SHIELD") (pin "3-38") (pinfunction "38_3-38") (pintype "passive"))
      (node (ref "SJ1") (pin "3") (pinfunction "3_3") (pintype "passive"))
    )
    (net (code "114") (name "LCD1_VSYNC{slash}PH27") (class "Default")
      (node (ref "A20_OLINUXINO_LIME2_SHIELD") (pin "3-40") (pinfunction "40_3-40") (pintype "passive"))
      (node (ref "SJ2") (pin "3") (pinfunction "3_3") (pintype "passive"))
    )
    (net (code "115") (name "LDO3_2.8V{slash}VCC_CSI0") (class "Default")
      (node (ref "A20_OLINUXINO_LIME2_SHIELD") (pin "2-4") (pinfunction "4_2-4") (pintype "passive"))
      (node (ref "R10") (pin "2") (pinfunction "2_2") (pintype "passive"))
    )
    (net (code "116") (name "LINEINL") (class "Default")
      (node (ref "A20_OLINUXINO_LIME2_SHIELD") (pin "4-15") (pinfunction "15_4-15") (pintype "passive"))
      (node (ref "SV2") (pin "3") (pinfunction "3_3") (pintype "passive"))
    )
    (net (code "117") (name "LINEINR") (class "Default")
      (node (ref "A20_OLINUXINO_LIME2_SHIELD") (pin "4-13") (pinfunction "13_4-13") (pintype "passive"))
      (node (ref "SV2") (pin "5") (pinfunction "5_5") (pintype "passive"))
    )
    (net (code "118") (name "LRADC0") (class "Default")
      (node (ref "A20_OLINUXINO_LIME2_SHIELD") (pin "1-6") (pinfunction "6_1-6") (pintype "passive"))
    )
    (net (code "119") (name "LRADC1") (class "Default")
      (node (ref "A20_OLINUXINO_LIME2_SHIELD") (pin "1-8") (pinfunction "8_1-8") (pintype "passive"))
    )
    (net (code "120") (name "MIC1OUTN") (class "Default")
      (node (ref "A20_OLINUXINO_LIME2_SHIELD") (pin "4-8") (pinfunction "8_4-8") (pintype "passive"))
    )
    (net (code "121") (name "MIC1OUTP") (class "Default")
      (node (ref "A20_OLINUXINO_LIME2_SHIELD") (pin "4-6") (pinfunction "6_4-6") (pintype "passive"))
    )
    (net (code "122") (name "MICIN1") (class "Default")
      (node (ref "A20_OLINUXINO_LIME2_SHIELD") (pin "1-10") (pinfunction "10_1-10") (pintype "passive"))
      (node (ref "JP2") (pin "2") (pinfunction "2_2") (pintype "passive"))
    )
    (net (code "123") (name "MICIN2") (class "Default")
      (node (ref "A20_OLINUXINO_LIME2_SHIELD") (pin "4-10") (pinfunction "10_4-10") (pintype "passive"))
      (node (ref "JP1") (pin "2") (pinfunction "2_2") (pintype "passive"))
    )
    (net (code "124") (name "NCE1{slash}PC3{slash}SATA-PWR-EN") (class "Default")
      (node (ref "A20_OLINUXINO_LIME2_SHIELD") (pin "1-29") (pinfunction "29_1-29") (pintype "passive"))
    )
    (net (code "125") (name "NCE2{slash}PC17") (class "Default")
      (node (ref "A20_OLINUXINO_LIME2_SHIELD") (pin "4-20") (pinfunction "20_4-20") (pintype "passive"))
    )
    (net (code "126") (name "NCE3{slash}PC18") (class "Default")
      (node (ref "A20_OLINUXINO_LIME2_SHIELD") (pin "1-31") (pinfunction "31_1-31") (pintype "passive"))
    )
    (net (code "127") (name "NC{slash}IR0_RX{slash}PB4") (class "Default")
      (node (ref "A20_OLINUXINO_LIME2_SHIELD") (pin "D-34") (pinfunction "34_D-34") (pintype "passive"))
    )
    (net (code "128") (name "NC{slash}IR0_TX{slash}SPDIF_MCLK{slash}STANBYWFI{slash}PB3") (class "Default")
      (node (ref "A20_OLINUXINO_LIME2_SHIELD") (pin "D-33") (pinfunction "33_D-33") (pintype "passive"))
    )
    (net (code "129") (name "NDQS{slash}PC24") (class "Default")
      (node (ref "A20_OLINUXINO_LIME2_SHIELD") (pin "1-38") (pinfunction "38_1-38") (pintype "passive"))
      (node (ref "X1") (pin "7") (pinfunction "MS_7") (pintype "passive"))
    )
    (net (code "130") (name "NMI_N") (class "Default")
      (node (ref "A20_OLINUXINO_LIME2_SHIELD") (pin "4-4") (pinfunction "4_4-4") (pintype "passive"))
    )
    (net (code "131") (name "NRB1{slash}SDC2_CLK{slash}PC7") (class "Default")
      (node (ref "A20_OLINUXINO_LIME2_SHIELD") (pin "4-16") (pinfunction "16_4-16") (pintype "passive"))
    )
    (net (code "132") (name "NWP{slash}PC16") (class "Default")
      (node (ref "A20_OLINUXINO_LIME2_SHIELD") (pin "4-18") (pinfunction "18_4-18") (pintype "passive"))
    )
    (net (code "133") (name "Net-(A20_OLINUXINO_LIME2_SHIELDB-6)") (class "Default")
      (node (ref "A20_OLINUXINO_LIME2_SHIELD") (pin "2-6") (pinfunction "6_2-6") (pintype "passive"))
      (node (ref "R8") (pin "2") (pinfunction "2_2") (pintype "passive"))
    )
    (net (code "134") (name "Net-(A20_OLINUXINO_LIME2_SHIELDB-8)") (class "Default")
      (node (ref "A20_OLINUXINO_LIME2_SHIELD") (pin "2-8") (pinfunction "8_2-8") (pintype "passive"))
      (node (ref "R9") (pin "2") (pinfunction "2_2") (pintype "passive"))
    )
    (net (code "135") (name "Net-(R6-Pad1)") (class "Default")
      (node (ref "R6") (pin "1") (pinfunction "1_1") (pintype "passive"))
      (node (ref "X5") (pin "4") (pinfunction "4_4") (pintype "passive"))
    )
    (net (code "136") (name "Net-(X1O-MS)") (class "Default")
      (node (ref "R1") (pin "2") (pinfunction "2_2") (pintype "passive"))
      (node (ref "X1") (pin "22") (pinfunction "MS_22") (pintype "passive"))
    )
    (net (code "137") (name "Net-(X4AF-MS)") (class "Default")
      (node (ref "R7") (pin "2") (pinfunction "2_2") (pintype "passive"))
      (node (ref "X4") (pin "38") (pinfunction "MS_38") (pintype "passive"))
      (node (ref "X4") (pin "40") (pinfunction "MS_40") (pintype "passive"))
    )
    (net (code "138") (name "Net-(X4W-MS)") (class "Default")
      (node (ref "R10") (pin "1") (pinfunction "1_1") (pintype "passive"))
      (node (ref "X4") (pin "3") (pinfunction "MS_3") (pintype "passive"))
    )
    (net (code "139") (name "PS2_SCK1{slash}TCLKIN0{slash}EINT26{slash}SPI0_CS1{slash}PI14") (class "Default")
      (node (ref "A20_OLINUXINO_LIME2_SHIELD") (pin "2-37") (pinfunction "37_2-37") (pintype "passive"))
    )
    (net (code "140") (name "PS2_SDA1{slash}TCLKIN1{slash}EINT27{slash}SPI1_CS1{slash}PI15") (class "Default")
      (node (ref "A20_OLINUXINO_LIME2_SHIELD") (pin "2-39") (pinfunction "39_2-39") (pintype "passive"))
    )
    (net (code "141") (name "PWM0") (class "Default")
      (node (ref "A20_OLINUXINO_LIME2_SHIELD") (pin "D-36") (pinfunction "36_D-36") (pintype "passive"))
      (node (ref "X1") (pin "10") (pinfunction "MS_10") (pintype "passive"))
    )
    (net (code "142") (name "RESET_N") (class "Default")
      (node (ref "A20_OLINUXINO_LIME2_SHIELD") (pin "3-5") (pinfunction "5_3-5") (pintype "passive"))
      (node (ref "X4") (pin "33") (pinfunction "MS_33") (pintype "passive"))
    )
    (net (code "143") (name "SDC3_CLK{slash}PI5") (class "Default")
      (node (ref "A20_OLINUXINO_LIME2_SHIELD") (pin "2-19") (pinfunction "19_2-19") (pintype "passive"))
    )
    (net (code "144") (name "SDC3_CMD{slash}PI4") (class "Default")
      (node (ref "A20_OLINUXINO_LIME2_SHIELD") (pin "2-17") (pinfunction "17_2-17") (pintype "passive"))
    )
    (net (code "145") (name "SDC3_D0{slash}PI6") (class "Default")
      (node (ref "A20_OLINUXINO_LIME2_SHIELD") (pin "2-21") (pinfunction "21_2-21") (pintype "passive"))
    )
    (net (code "146") (name "SDC3_D1{slash}PI7") (class "Default")
      (node (ref "A20_OLINUXINO_LIME2_SHIELD") (pin "2-23") (pinfunction "23_2-23") (pintype "passive"))
    )
    (net (code "147") (name "SDC3_D2{slash}PI8") (class "Default")
      (node (ref "A20_OLINUXINO_LIME2_SHIELD") (pin "2-25") (pinfunction "25_2-25") (pintype "passive"))
    )
    (net (code "148") (name "SDC3_D3{slash}PI9") (class "Default")
      (node (ref "A20_OLINUXINO_LIME2_SHIELD") (pin "2-27") (pinfunction "27_2-27") (pintype "passive"))
    )
    (net (code "149") (name "SPI0_CLK{slash}UART5_RX{slash}EINT23{slash}PI11") (class "Default")
      (node (ref "A20_OLINUXINO_LIME2_SHIELD") (pin "2-31") (pinfunction "31_2-31") (pintype "passive"))
    )
    (net (code "150") (name "SPI0_CS0{slash}PC23") (class "Default")
      (node (ref "A20_OLINUXINO_LIME2_SHIELD") (pin "1-40") (pinfunction "40_1-40") (pintype "passive"))
      (node (ref "X1") (pin "8") (pinfunction "MS_8") (pintype "passive"))
    )
    (net (code "151") (name "SPI0_CS0{slash}UART5_TX{slash}EINT22{slash}PI10") (class "Default")
      (node (ref "A20_OLINUXINO_LIME2_SHIELD") (pin "2-29") (pinfunction "29_2-29") (pintype "passive"))
    )
    (net (code "152") (name "SPI0_MISO{slash}UART6_RX{slash}EINT25{slash}PI13") (class "Default")
      (node (ref "A20_OLINUXINO_LIME2_SHIELD") (pin "2-35") (pinfunction "35_2-35") (pintype "passive"))
    )
    (net (code "153") (name "SPI0_MOSI{slash}UART6_TX{slash}EINT24{slash}PI12") (class "Default")
      (node (ref "A20_OLINUXINO_LIME2_SHIELD") (pin "2-33") (pinfunction "33_2-33") (pintype "passive"))
    )
    (net (code "154") (name "SPI2_CS1{slash}SPDIF_DO{slash}PB13") (class "Default")
      (node (ref "A20_OLINUXINO_LIME2_SHIELD") (pin "3-24") (pinfunction "24_3-24") (pintype "passive"))
    )
    (net (code "155") (name "TS1_ERR{slash}CSI1_MLCK{slash}SDC1_CLK{slash}PG1") (class "Default")
      (node (ref "A20_OLINUXINO_LIME2_SHIELD") (pin "1-7") (pinfunction "7_1-7") (pintype "passive"))
      (node (ref "LSP4") (pin "MP") (pinfunction "MP_MP") (pintype "passive"))
    )
    (net (code "156") (name "TVIN0") (class "Default")
      (node (ref "A20_OLINUXINO_LIME2_SHIELD") (pin "4-5") (pinfunction "5_4-5") (pintype "passive"))
    )
    (net (code "157") (name "TVIN1") (class "Default")
      (node (ref "A20_OLINUXINO_LIME2_SHIELD") (pin "4-7") (pinfunction "7_4-7") (pintype "passive"))
    )
    (net (code "158") (name "TVIN2") (class "Default")
      (node (ref "A20_OLINUXINO_LIME2_SHIELD") (pin "4-9") (pinfunction "9_4-9") (pintype "passive"))
    )
    (net (code "159") (name "TVIN3") (class "Default")
      (node (ref "A20_OLINUXINO_LIME2_SHIELD") (pin "4-11") (pinfunction "11_4-11") (pintype "passive"))
    )
    (net (code "160") (name "TVOUT0{slash}VGA-G") (class "Default")
      (node (ref "A20_OLINUXINO_LIME2_SHIELD") (pin "1-20") (pinfunction "20_1-20") (pintype "passive"))
      (node (ref "X2") (pin "2") (pinfunction "F_2") (pintype "passive"))
    )
    (net (code "161") (name "TVOUT1{slash}VGA-B") (class "Default")
      (node (ref "A20_OLINUXINO_LIME2_SHIELD") (pin "1-22") (pinfunction "22_1-22") (pintype "passive"))
      (node (ref "X2") (pin "3") (pinfunction "F_3") (pintype "passive"))
    )
    (net (code "162") (name "TVOUT2{slash}VGA-R") (class "Default")
      (node (ref "A20_OLINUXINO_LIME2_SHIELD") (pin "1-24") (pinfunction "24_1-24") (pintype "passive"))
      (node (ref "X2") (pin "1") (pinfunction "F_1") (pintype "passive"))
    )
    (net (code "163") (name "TVOUT3") (class "Default")
      (node (ref "A20_OLINUXINO_LIME2_SHIELD") (pin "4-3") (pinfunction "3_4-3") (pintype "passive"))
      (node (ref "SV2") (pin "6") (pinfunction "6_6") (pintype "passive"))
    )
    (net (code "164") (name "TWI0_SCK{slash}PB0") (class "Default")
      (node (ref "A20_OLINUXINO_LIME2_SHIELD") (pin "2-5") (pinfunction "5_2-5") (pintype "passive"))
    )
    (net (code "165") (name "TWI0_SDA{slash}PB1") (class "Default")
      (node (ref "A20_OLINUXINO_LIME2_SHIELD") (pin "2-7") (pinfunction "7_2-7") (pintype "passive"))
    )
    (net (code "166") (name "TWI1_SCK{slash}PB18") (class "Default")
      (node (ref "A20_OLINUXINO_LIME2_SHIELD") (pin "1-36") (pinfunction "36_1-36") (pintype "passive"))
    )
    (net (code "167") (name "TWI1_SDA{slash}PB19") (class "Default")
      (node (ref "A20_OLINUXINO_LIME2_SHIELD") (pin "1-34") (pinfunction "34_1-34") (pintype "passive"))
    )
    (net (code "168") (name "TWI2_SCK{slash}PB20") (class "Default")
      (node (ref "A20_OLINUXINO_LIME2_SHIELD") (pin "1-32") (pinfunction "32_1-32") (pintype "passive"))
      (node (ref "R4") (pin "1") (pinfunction "1_1") (pintype "passive"))
      (node (ref "T2") (pin "2") (pinfunction "S_2") (pintype "passive"))
    )
    (net (code "169") (name "TWI2_SDA{slash}PB21") (class "Default")
      (node (ref "A20_OLINUXINO_LIME2_SHIELD") (pin "1-30") (pinfunction "30_1-30") (pintype "passive"))
      (node (ref "R2") (pin "1") (pinfunction "1_1") (pintype "passive"))
      (node (ref "T1") (pin "2") (pinfunction "S_2") (pintype "passive"))
    )
    (net (code "170") (name "UART0_RX{slash}IR1_RX{slash}PB23") (class "Default")
      (node (ref "A20_OLINUXINO_LIME2_SHIELD") (pin "1-26") (pinfunction "26_1-26") (pintype "passive"))
    )
    (net (code "171") (name "UART0_TX{slash}IR1_TX{slash}PB22") (class "Default")
      (node (ref "A20_OLINUXINO_LIME2_SHIELD") (pin "1-28") (pinfunction "28_1-28") (pintype "passive"))
    )
    (net (code "172") (name "VGA-HSYNC") (class "Default")
      (node (ref "SJ1") (pin "2") (pinfunction "2_2") (pintype "passive"))
      (node (ref "X2") (pin "13") (pinfunction "F_13") (pintype "passive"))
    )
    (net (code "173") (name "VGA-VSYNC") (class "Default")
      (node (ref "SJ2") (pin "2") (pinfunction "2_2") (pintype "passive"))
      (node (ref "X2") (pin "14") (pinfunction "F_14") (pintype "passive"))
    )
    (net (code "174") (name "VMIC") (class "Default")
      (node (ref "A20_OLINUXINO_LIME2_SHIELD") (pin "1-12") (pinfunction "12_1-12") (pintype "passive"))
    )
    (net (code "175") (name "XN_TP") (class "Default")
      (node (ref "A20_OLINUXINO_LIME2_SHIELD") (pin "D-38") (pinfunction "38_D-38") (pintype "passive"))
    )
    (net (code "176") (name "XP_TP") (class "Default")
      (node (ref "A20_OLINUXINO_LIME2_SHIELD") (pin "D-37") (pinfunction "37_D-37") (pintype "passive"))
    )
    (net (code "177") (name "YN_TP") (class "Default")
      (node (ref "A20_OLINUXINO_LIME2_SHIELD") (pin "D-40") (pinfunction "40_D-40") (pintype "passive"))
    )
    (net (code "178") (name "YP_TP") (class "Default")
      (node (ref "A20_OLINUXINO_LIME2_SHIELD") (pin "D-39") (pinfunction "39_D-39") (pintype "passive"))
    )
    (net (code "179") (name "unconnected-(SV1-SRST-Pad6)") (class "Default")
      (node (ref "SV1") (pin "6") (pinfunction "SRST_6") (pintype "output"))
    )
    (net (code "180") (name "unconnected-(SV1-TRST-Pad8)") (class "Default")
      (node (ref "SV1") (pin "8") (pinfunction "TRST_8") (pintype "output"))
    )
    (net (code "181") (name "unconnected-(X1AH-MS-Pad4)") (class "Default")
      (node (ref "X1") (pin "4") (pinfunction "MS_4") (pintype "passive"))
    )
    (net (code "182") (name "unconnected-(X1AK-MS-Pad6)") (class "Default")
      (node (ref "X1") (pin "6") (pinfunction "MS_6") (pintype "passive"))
    )
    (net (code "183") (name "unconnected-(X1D-MS-Pad12)") (class "Default")
      (node (ref "X1") (pin "12") (pinfunction "MS_12") (pintype "passive"))
    )
    (net (code "184") (name "unconnected-(X1L-MS-Pad2)") (class "Default")
      (node (ref "X1") (pin "2") (pinfunction "MS_2") (pintype "passive"))
    )
    (net (code "185") (name "unconnected-(X1M-MS-Pad20)") (class "Default")
      (node (ref "X1") (pin "20") (pinfunction "MS_20") (pintype "passive"))
    )
    (net (code "186") (name "unconnected-(X2C-F-Pad11)") (class "Default")
      (node (ref "X2") (pin "11") (pinfunction "F_11") (pintype "passive"))
    )
    (net (code "187") (name "unconnected-(X2J-F-Pad4)") (class "Default")
      (node (ref "X2") (pin "4") (pinfunction "F_4") (pintype "passive"))
    )
    (net (code "188") (name "unconnected-(X4A-MSV-Pad1)") (class "Default")
      (node (ref "X4") (pin "1") (pinfunction "MSV_1") (pintype "passive"))
    )
    (net (code "189") (name "unconnected-(X4AB-MS-Pad34)") (class "Default")
      (node (ref "X4") (pin "34") (pinfunction "MS_34") (pintype "passive"))
    )
    (net (code "190") (name "unconnected-(X4AD-MS-Pad36)") (class "Default")
      (node (ref "X4") (pin "36") (pinfunction "MS_36") (pintype "passive"))
    )
    (net (code "191") (name "unconnected-(X4AE-MS-Pad37)") (class "Default")
      (node (ref "X4") (pin "37") (pinfunction "MS_37") (pintype "passive"))
    )
    (net (code "192") (name "unconnected-(X4AH-MS-Pad4)") (class "Default")
      (node (ref "X4") (pin "4") (pinfunction "MS_4") (pintype "passive"))
    )
    (net (code "193") (name "unconnected-(X4AK-MS-Pad6)") (class "Default")
      (node (ref "X4") (pin "6") (pinfunction "MS_6") (pintype "passive"))
    )
    (net (code "194") (name "unconnected-(X4AL-MS-Pad7)") (class "Default")
      (node (ref "X4") (pin "7") (pinfunction "MS_7") (pintype "passive"))
    )
    (net (code "195") (name "unconnected-(X4AM-MS-Pad8)") (class "Default")
      (node (ref "X4") (pin "8") (pinfunction "MS_8") (pintype "passive"))
    )
    (net (code "196") (name "unconnected-(X4AN-MS-Pad9)") (class "Default")
      (node (ref "X4") (pin "9") (pinfunction "MS_9") (pintype "passive"))
    )
    (net (code "197") (name "unconnected-(X4B-MS-Pad10)") (class "Default")
      (node (ref "X4") (pin "10") (pinfunction "MS_10") (pintype "passive"))
    )
    (net (code "198") (name "unconnected-(X4E-MS-Pad13)") (class "Default")
      (node (ref "X4") (pin "13") (pinfunction "MS_13") (pintype "passive"))
    )
    (net (code "199") (name "unconnected-(X4F-MS-Pad14)") (class "Default")
      (node (ref "X4") (pin "14") (pinfunction "MS_14") (pintype "passive"))
    )
    (net (code "200") (name "unconnected-(X4G-MS-Pad15)") (class "Default")
      (node (ref "X4") (pin "15") (pinfunction "MS_15") (pintype "passive"))
    )
    (net (code "201") (name "unconnected-(X4H-MS-Pad16)") (class "Default")
      (node (ref "X4") (pin "16") (pinfunction "MS_16") (pintype "passive"))
    )
    (net (code "202") (name "unconnected-(X4L-MS-Pad2)") (class "Default")
      (node (ref "X4") (pin "2") (pinfunction "MS_2") (pintype "passive"))
    )
    (net (code "203") (name "unconnected-(X4Z-MS-Pad32)") (class "Default")
      (node (ref "X4") (pin "32") (pinfunction "MS_32") (pintype "passive"))
    )
    (net (code "204") (name "unconnected-(X5-Pad1)") (class "Default")
      (node (ref "X5") (pin "1") (pinfunction "1_1") (pintype "passive"))
    )
    (net (code "205") (name "unconnected-(X5-Pad2)") (class "Default")
      (node (ref "X5") (pin "2") (pinfunction "2_2") (pintype "passive"))
    )
    (net (code "206") (name "unconnected-(X5-Pad35)") (class "Default")
      (node (ref "X5") (pin "35") (pinfunction "35_35") (pintype "passive"))
    )
    (net (code "207") (name "unconnected-(X5-Pad37)") (class "Default")
      (node (ref "X5") (pin "37") (pinfunction "37_37") (pintype "passive"))
    )
    (net (code "208") (name "unconnected-(X5-Pad38)") (class "Default")
      (node (ref "X5") (pin "38") (pinfunction "38_38") (pintype "passive"))
    )
    (net (code "209") (name "unconnected-(X5-Pad39)") (class "Default")
      (node (ref "X5") (pin "39") (pinfunction "39_39") (pintype "passive"))
    )
    (net (code "210") (name "unconnected-(X5-Pad40)") (class "Default")
      (node (ref "X5") (pin "40") (pinfunction "40_40") (pintype "passive"))
    )
  )
)
